# SPE_router_e-fuse_3A.net
KiCad netlist of a schematic drawn in Altium Designer
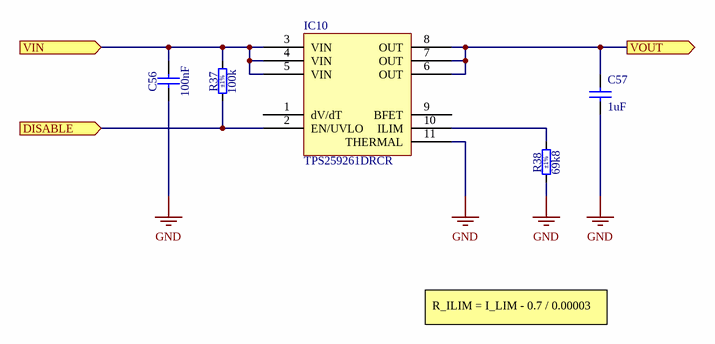
[diagram p0: SPE_router_e-fuse_3A.SchDoc]

(export (version "E")
  (design (tool "Eeschema 10.0.6"))
  (components
    (comp (ref "C56")
      (value "100nF")
      (footprint "CAPC1005X55N")
      (description "Non-polarised capacitor")
      (fields
        (field (name "PART NUMBER") "CC0402_100NF_16V_10%_X7R")
        (field (name "VOLTAGE") "16V")
        (field (name "AUTHOR") "CERN DEM JLC")
      )
      (libsource (lib "Capacitors") (part "Capacitor - non polarized"))
    )
    (comp (ref "C57")
      (value "1uF")
      (footprint "CAPC1005X55N")
      (description "Non-polarised capacitor")
      (fields
        (field (name "PART NUMBER") "CC0402_1UF_16V_10%_X5R")
        (field (name "VOLTAGE") "16V")
        (field (name "AUTHOR") "CERN DEM JLC")
      )
      (libsource (lib "Capacitors") (part "Capacitor - non polarized"))
    )
    (comp (ref "IC10")
      (value "TPS259261DRCR")
      (footprint "VSON50P300X100_HS-11N")
      (description "Hot Swap Controller 13.8V Positive Voltage 10-Pin VSON EP T/R")
      (fields (field (name "MANUFACTURER") "Texas Instruments"))
      (libsource (lib "SPE_router_lib") (part "TPS259261DRCR"))
    )
    (comp (ref "R37")
      (value "100k")
      (footprint "RESC1005X40N")
      (description "Resistor - 1%")
      (fields
        (field (name "TOLERANCE") "±1%")
        (field (name "PART NUMBER") "R0402_100K_1%_0.0625W_100PPM")
        (field (name "POWER") "0.0625W")
        (field (name "AUTHOR") "CERN DEM JLC")
      )
      (libsource (lib "Resistors") (part "Resistor - 1%"))
    )
    (comp (ref "R38")
      (value "69k8")
      (footprint "RESC1005X40N")
      (description "Resistor - 1%")
      (fields
        (field (name "TOLERANCE") "±1%")
        (field (name "PART NUMBER") "R0402_69K8_1%_0.063W_100PPM")
        (field (name "POWER") "0.063W")
        (field (name "AUTHOR") "CERN DEM BC")
      )
      (libsource (lib "Resistors") (part "Resistor - 1%"))
    )
  )
  (nets
    (net (code "1") (name "/DISABLE") (class "Default")
      (node (ref "IC10") (pin "2") (pinfunction "EN/UVLO_2") (pintype "passive"))
      (node (ref "R37") (pin "1") (pinfunction "1_1") (pintype "passive"))
    )
    (net (code "2") (name "/VIN") (class "Default")
      (node (ref "C56") (pin "2") (pinfunction "2_2") (pintype "passive"))
      (node (ref "IC10") (pin "3") (pinfunction "VIN_3") (pintype "passive"))
      (node (ref "IC10") (pin "4") (pinfunction "VIN_4") (pintype "passive"))
      (node (ref "IC10") (pin "5") (pinfunction "VIN_5") (pintype "passive"))
      (node (ref "R37") (pin "2") (pinfunction "2_2") (pintype "passive"))
    )
    (net (code "3") (name "/VOUT") (class "Default")
      (node (ref "C57") (pin "2") (pinfunction "2_2") (pintype "passive"))
      (node (ref "IC10") (pin "6") (pinfunction "OUT_6") (pintype "passive"))
      (node (ref "IC10") (pin "7") (pinfunction "OUT_7") (pintype "passive"))
      (node (ref "IC10") (pin "8") (pinfunction "OUT_8") (pintype "passive"))
    )
    (net (code "4") (name "GND") (class "Default")
      (node (ref "C56") (pin "1") (pinfunction "1_1") (pintype "passive"))
      (node (ref "C57") (pin "1") (pinfunction "1_1") (pintype "passive"))
      (node (ref "IC10") (pin "11") (pinfunction "THERMAL_11") (pintype "passive"))
      (node (ref "R38") (pin "1") (pinfunction "1_1") (pintype "passive"))
    )
    (net (code "5") (name "Net-(IC10-ILIM)") (class "Default")
      (node (ref "IC10") (pin "10") (pinfunction "ILIM_10") (pintype "passive"))
      (node (ref "R38") (pin "2") (pinfunction "2_2") (pintype "passive"))
    )
    (net (code "6") (name "unconnected-(IC10-BFET-Pad9)") (class "Default")
      (node (ref "IC10") (pin "9") (pinfunction "BFET_9") (pintype "passive"))
    )
    (net (code "7") (name "unconnected-(IC10-dV{slash}dT-Pad1)") (class "Default")
      (node (ref "IC10") (pin "1") (pinfunction "dV/dT_1") (pintype "passive"))
    )
  )
)
